# B301B.net
KiCad netlist of a schematic drawn in EAGLE
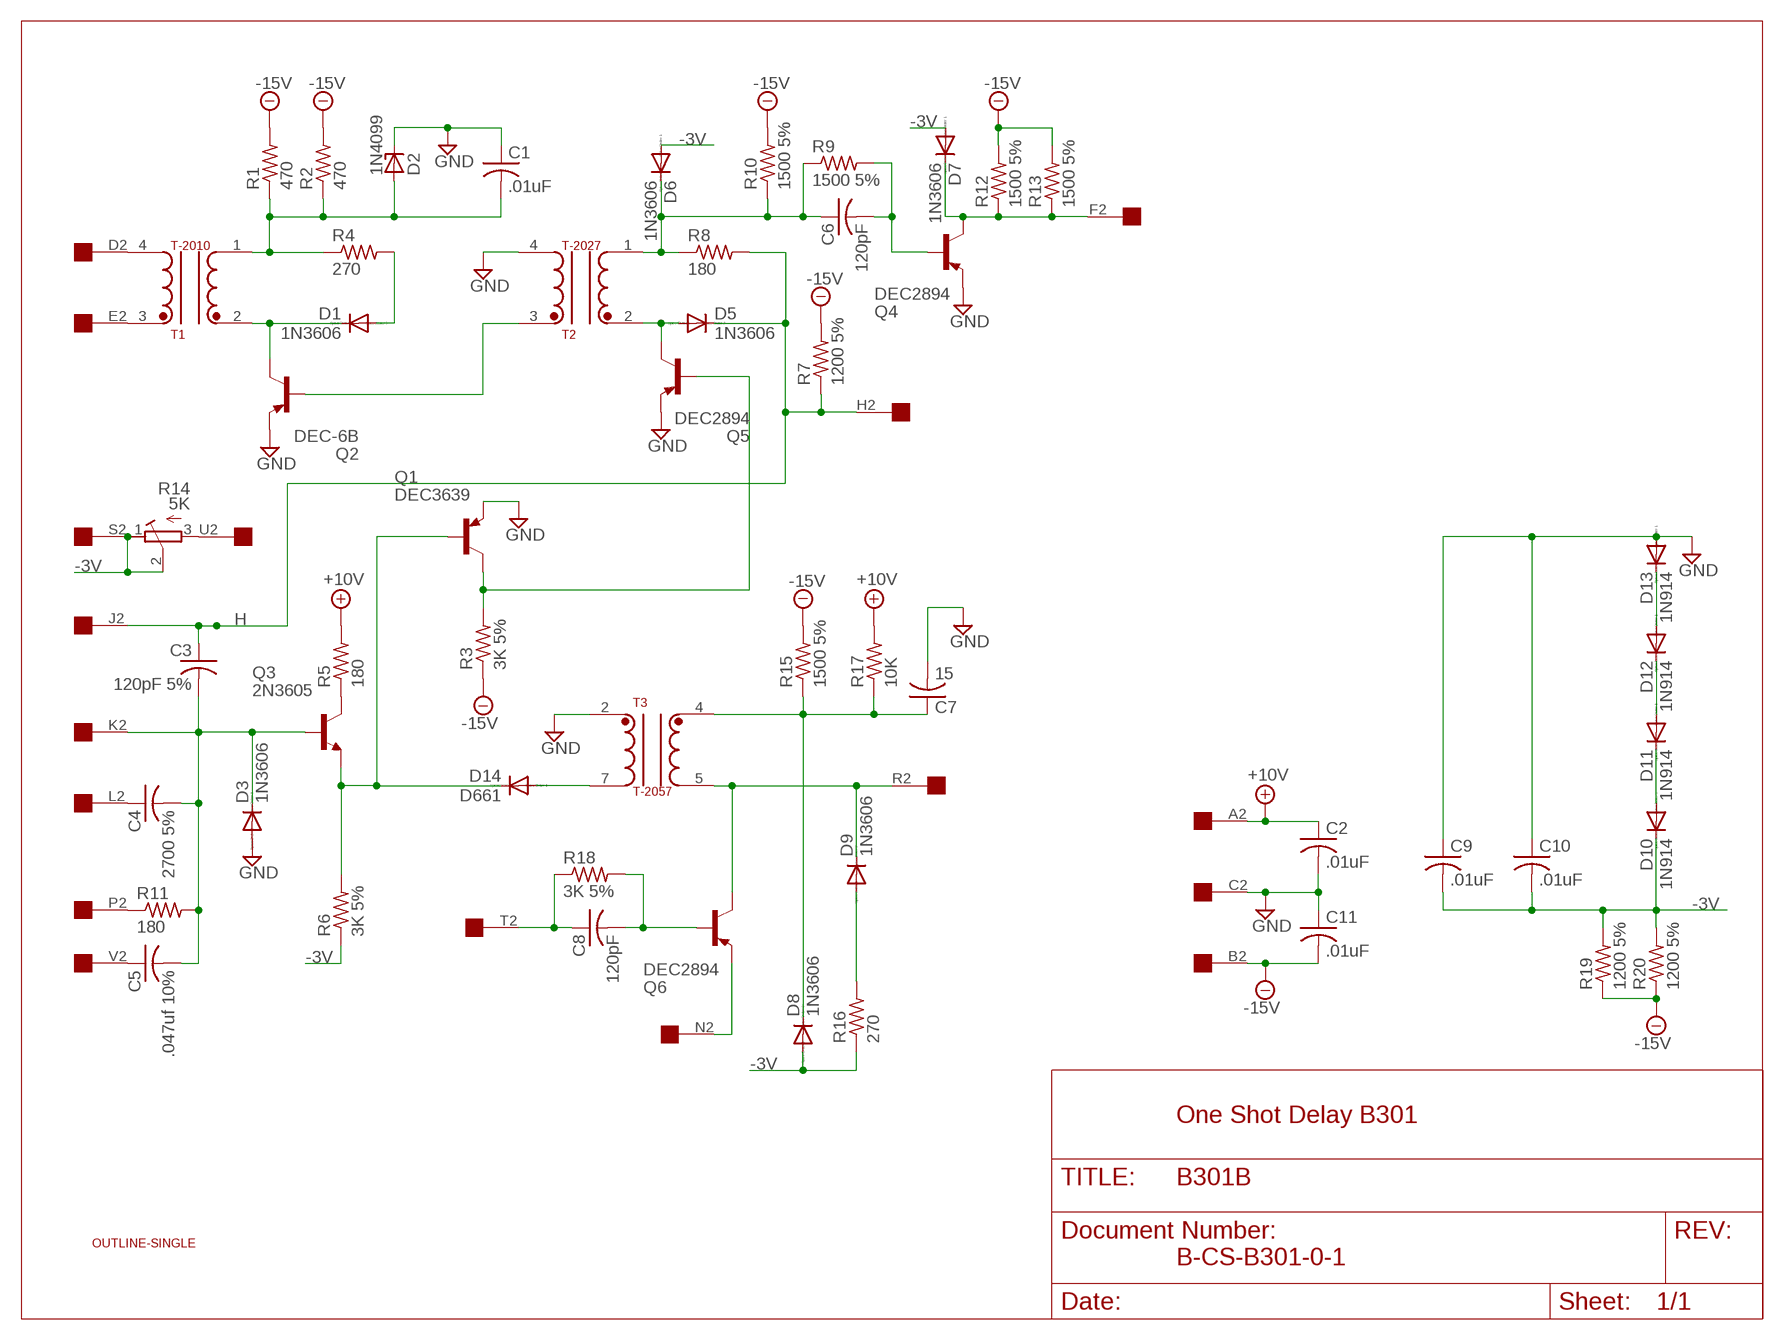
[diagram p0: schematic, sheet 1]

(export (version "E")
  (design (tool "Eeschema 10.0.6"))
  (components
    (comp (ref "C1")
      (value ".01uF")
      (footprint "eagle-import:C050-025X075")
      (libsource (lib "eagle-import") (part "C-US050-025X075"))
    )
    (comp (ref "C2")
      (value ".01uF")
      (footprint "eagle-import:C050-025X075")
      (libsource (lib "eagle-import") (part "C-US050-025X075"))
    )
    (comp (ref "C3")
      (value "120pF 5%")
      (footprint "eagle-import:C050-025X075")
      (libsource (lib "eagle-import") (part "C-US050-025X075"))
    )
    (comp (ref "C4")
      (value "2700 5%")
      (footprint "eagle-import:C102-043X133")
      (libsource (lib "eagle-import") (part "C-US102-043X133"))
    )
    (comp (ref "C5")
      (value ".047uf 10%")
      (footprint "eagle-import:C225-062X268")
      (libsource (lib "eagle-import") (part "C-US225-062X268"))
    )
    (comp (ref "C6")
      (value "120pF")
      (footprint "eagle-import:C050-025X075")
      (libsource (lib "eagle-import") (part "C-US050-025X075"))
    )
    (comp (ref "C7")
      (value "15")
      (footprint "eagle-import:C050-025X075")
      (libsource (lib "eagle-import") (part "C-US050-025X075"))
    )
    (comp (ref "C8")
      (value "120pF")
      (footprint "eagle-import:C050-025X075")
      (libsource (lib "eagle-import") (part "C-US050-025X075"))
    )
    (comp (ref "C9")
      (value ".01uF")
      (footprint "eagle-import:C050-025X075")
      (libsource (lib "eagle-import") (part "C-US050-025X075"))
    )
    (comp (ref "C10")
      (value ".01uF")
      (footprint "eagle-import:C050-025X075")
      (libsource (lib "eagle-import") (part "C-US050-025X075"))
    )
    (comp (ref "C11")
      (value ".01uF")
      (footprint "eagle-import:C050-025X075")
      (libsource (lib "eagle-import") (part "C-US050-025X075"))
    )
    (comp (ref "D1")
      (value "1N3606")
      (footprint "eagle-import:DO35-10")
      (libsource (lib "eagle-import") (part "1N4148DO35-10"))
    )
    (comp (ref "D2")
      (value "1N4099")
      (footprint "eagle-import:DO35Z10")
      (libsource (lib "eagle-import") (part "ZENER-DIODEDO35Z10"))
    )
    (comp (ref "D3")
      (value "1N3606")
      (footprint "eagle-import:DO35-10")
      (libsource (lib "eagle-import") (part "1N4148DO35-10"))
    )
    (comp (ref "D5")
      (value "1N3606")
      (footprint "eagle-import:DO35-10")
      (libsource (lib "eagle-import") (part "1N4148DO35-10"))
    )
    (comp (ref "D6")
      (value "1N3606")
      (footprint "eagle-import:DO35-10")
      (libsource (lib "eagle-import") (part "1N4148DO35-10"))
    )
    (comp (ref "D7")
      (value "1N3606")
      (footprint "eagle-import:DO35-10")
      (libsource (lib "eagle-import") (part "1N4148DO35-10"))
    )
    (comp (ref "D8")
      (value "1N3606")
      (footprint "eagle-import:DO35-10")
      (libsource (lib "eagle-import") (part "1N4148DO35-10"))
    )
    (comp (ref "D9")
      (value "1N3606")
      (footprint "eagle-import:DO35-10")
      (libsource (lib "eagle-import") (part "1N4148DO35-10"))
    )
    (comp (ref "D10")
      (value "1N914")
      (footprint "eagle-import:DO35-10")
      (libsource (lib "eagle-import") (part "1N4148DO35-10"))
    )
    (comp (ref "D11")
      (value "1N914")
      (footprint "eagle-import:DO35-10")
      (libsource (lib "eagle-import") (part "1N4148DO35-10"))
    )
    (comp (ref "D12")
      (value "1N914")
      (footprint "eagle-import:DO35-10")
      (libsource (lib "eagle-import") (part "1N4148DO35-10"))
    )
    (comp (ref "D13")
      (value "1N914")
      (footprint "eagle-import:DO35-10")
      (libsource (lib "eagle-import") (part "1N4148DO35-10"))
    )
    (comp (ref "D14")
      (value "D661")
      (footprint "eagle-import:DO35-10")
      (libsource (lib "eagle-import") (part "1N4148DO35-10"))
    )
    (comp (ref "Q1")
      (value "DEC3639")
      (footprint "eagle-import:TO39")
      (libsource (lib "eagle-import") (part "2N2904"))
    )
    (comp (ref "Q2")
      (value "DEC-6B")
      (footprint "eagle-import:TO39")
      (libsource (lib "eagle-import") (part "2N2904"))
    )
    (comp (ref "Q3")
      (value "2N3605")
      (footprint "eagle-import:TO39")
      (libsource (lib "eagle-import") (part "-NPN-TO39-EBC2N2102"))
    )
    (comp (ref "Q4")
      (value "DEC2894")
      (footprint "eagle-import:TO39")
      (libsource (lib "eagle-import") (part "2N2904"))
    )
    (comp (ref "Q5")
      (value "DEC2894")
      (footprint "eagle-import:TO39")
      (libsource (lib "eagle-import") (part "2N2904"))
    )
    (comp (ref "Q6")
      (value "DEC2894")
      (footprint "eagle-import:TO39")
      (libsource (lib "eagle-import") (part "2N2904"))
    )
    (comp (ref "R1")
      (value "470")
      (footprint "eagle-import:0207_10")
      (libsource (lib "eagle-import") (part "R-US_0207/10"))
    )
    (comp (ref "R2")
      (value "470")
      (footprint "eagle-import:0207_10")
      (libsource (lib "eagle-import") (part "R-US_0207/10"))
    )
    (comp (ref "R3")
      (value "3K 5%")
      (footprint "eagle-import:0207_10")
      (libsource (lib "eagle-import") (part "R-US_0207/10"))
    )
    (comp (ref "R4")
      (value "270")
      (footprint "eagle-import:0207_10")
      (libsource (lib "eagle-import") (part "R-US_0207/10"))
    )
    (comp (ref "R5")
      (value "180")
      (footprint "eagle-import:0207_10")
      (libsource (lib "eagle-import") (part "R-US_0207/10"))
    )
    (comp (ref "R6")
      (value "3K 5%")
      (footprint "eagle-import:0207_10")
      (libsource (lib "eagle-import") (part "R-US_0207/10"))
    )
    (comp (ref "R7")
      (value "1200 5%")
      (footprint "eagle-import:0207_10")
      (libsource (lib "eagle-import") (part "R-US_0207/10"))
    )
    (comp (ref "R8")
      (value "180")
      (footprint "eagle-import:0207_10")
      (libsource (lib "eagle-import") (part "R-US_0207/10"))
    )
    (comp (ref "R9")
      (value "1500 5%")
      (footprint "eagle-import:0207_10")
      (libsource (lib "eagle-import") (part "R-US_0207/10"))
    )
    (comp (ref "R10")
      (value "1500 5%")
      (footprint "eagle-import:0207_10")
      (libsource (lib "eagle-import") (part "R-US_0207/10"))
    )
    (comp (ref "R11")
      (value "180")
      (footprint "eagle-import:0207_10")
      (libsource (lib "eagle-import") (part "R-US_0207/10"))
    )
    (comp (ref "R12")
      (value "1500 5%")
      (footprint "eagle-import:0207_10")
      (libsource (lib "eagle-import") (part "R-US_0207/10"))
    )
    (comp (ref "R13")
      (value "1500 5%")
      (footprint "eagle-import:0207_10")
      (libsource (lib "eagle-import") (part "R-US_0207/10"))
    )
    (comp (ref "R14")
      (value "5K")
      (footprint "eagle-import:3006Y")
      (libsource (lib "eagle-import") (part "275P"))
    )
    (comp (ref "R15")
      (value "1500 5%")
      (footprint "eagle-import:0207_10")
      (libsource (lib "eagle-import") (part "R-US_0207/10"))
    )
    (comp (ref "R16")
      (value "270")
      (footprint "eagle-import:0207_10")
      (libsource (lib "eagle-import") (part "R-US_0207/10"))
    )
    (comp (ref "R17")
      (value "10K")
      (footprint "eagle-import:0207_10")
      (libsource (lib "eagle-import") (part "R-US_0207/10"))
    )
    (comp (ref "R18")
      (value "3K 5%")
      (footprint "eagle-import:0207_10")
      (libsource (lib "eagle-import") (part "R-US_0207/10"))
    )
    (comp (ref "R19")
      (value "1200 5%")
      (footprint "eagle-import:0207_10")
      (libsource (lib "eagle-import") (part "R-US_0207/10"))
    )
    (comp (ref "R20")
      (value "1200 5%")
      (footprint "eagle-import:0207_10")
      (libsource (lib "eagle-import") (part "R-US_0207/10"))
    )
    (comp (ref "T1")
      (value "T-2010")
      (footprint "eagle-import:TRANSFORMER2")
      (libsource (lib "eagle-import") (part "T-2010"))
    )
    (comp (ref "T2")
      (value "T-2027")
      (footprint "eagle-import:TRANSFORMER2")
      (libsource (lib "eagle-import") (part "T-2010"))
    )
    (comp (ref "T3")
      (value "T-2057")
      (footprint "eagle-import:TRANSFORMER")
      (libsource (lib "eagle-import") (part "T-2037"))
    )
    (comp (ref "U$1")
      (value "OUTLINE-SINGLE")
      (footprint "eagle-import:SINGLE")
      (libsource (lib "eagle-import") (part "OUTLINE-SINGLE"))
    )
    (comp (ref "U$2")
      (value "EDGE-1")
      (footprint "eagle-import:EDGE-CON1")
      (libsource (lib "eagle-import") (part "EDGE-1"))
    )
  )
  (nets
    (net (code "1") (name "+10V") (class "Default")
      (node (ref "C2") (pin "1") (pinfunction "1_1") (pintype "passive"))
      (node (ref "R17") (pin "2") (pinfunction "2_2") (pintype "passive"))
      (node (ref "R5") (pin "2") (pinfunction "2_2") (pintype "passive"))
      (node (ref "U$2") (pin "A2") (pinfunction "1_A2") (pintype "bidirectional"))
    )
    (net (code "2") (name "-15V") (class "Default")
      (node (ref "C11") (pin "2") (pinfunction "2_2") (pintype "passive"))
      (node (ref "R1") (pin "2") (pinfunction "2_2") (pintype "passive"))
      (node (ref "R10") (pin "2") (pinfunction "2_2") (pintype "passive"))
      (node (ref "R12") (pin "2") (pinfunction "2_2") (pintype "passive"))
      (node (ref "R13") (pin "2") (pinfunction "2_2") (pintype "passive"))
      (node (ref "R15") (pin "2") (pinfunction "2_2") (pintype "passive"))
      (node (ref "R19") (pin "1") (pinfunction "1_1") (pintype "passive"))
      (node (ref "R2") (pin "2") (pinfunction "2_2") (pintype "passive"))
      (node (ref "R20") (pin "1") (pinfunction "1_1") (pintype "passive"))
      (node (ref "R3") (pin "1") (pinfunction "1_1") (pintype "passive"))
      (node (ref "R7") (pin "2") (pinfunction "2_2") (pintype "passive"))
      (node (ref "U$2") (pin "B2") (pinfunction "1_B2") (pintype "bidirectional"))
    )
    (net (code "3") (name "/-3V") (class "Default")
      (node (ref "C10") (pin "2") (pinfunction "2_2") (pintype "passive"))
      (node (ref "C9") (pin "2") (pinfunction "2_2") (pintype "passive"))
      (node (ref "D10") (pin "C") (pinfunction "C_C") (pintype "passive"))
      (node (ref "D6") (pin "A") (pinfunction "A_A") (pintype "passive"))
      (node (ref "D7") (pin "A") (pinfunction "A_A") (pintype "passive"))
      (node (ref "D8") (pin "A") (pinfunction "A_A") (pintype "passive"))
      (node (ref "R14") (pin "1") (pinfunction "A_1") (pintype "passive"))
      (node (ref "R14") (pin "2") (pinfunction "S_2") (pintype "passive"))
      (node (ref "R16") (pin "1") (pinfunction "1_1") (pintype "passive"))
      (node (ref "R19") (pin "2") (pinfunction "2_2") (pintype "passive"))
      (node (ref "R20") (pin "2") (pinfunction "2_2") (pintype "passive"))
      (node (ref "R6") (pin "1") (pinfunction "1_1") (pintype "passive"))
      (node (ref "U$2") (pin "S2") (pinfunction "1_S2") (pintype "bidirectional"))
    )
    (net (code "4") (name "/H") (class "Default")
      (node (ref "C3") (pin "1") (pinfunction "1_1") (pintype "passive"))
      (node (ref "D5") (pin "C") (pinfunction "C_C") (pintype "passive"))
      (node (ref "R7") (pin "1") (pinfunction "1_1") (pintype "passive"))
      (node (ref "R8") (pin "2") (pinfunction "2_2") (pintype "passive"))
      (node (ref "U$2") (pin "H2") (pinfunction "1_H2") (pintype "bidirectional"))
      (node (ref "U$2") (pin "J2") (pinfunction "1_J2") (pintype "bidirectional"))
    )
    (net (code "5") (name "GND") (class "Default")
      (node (ref "C1") (pin "1") (pinfunction "1_1") (pintype "passive"))
      (node (ref "C10") (pin "1") (pinfunction "1_1") (pintype "passive"))
      (node (ref "C11") (pin "1") (pinfunction "1_1") (pintype "passive"))
      (node (ref "C2") (pin "2") (pinfunction "2_2") (pintype "passive"))
      (node (ref "C7") (pin "2") (pinfunction "2_2") (pintype "passive"))
      (node (ref "C9") (pin "1") (pinfunction "1_1") (pintype "passive"))
      (node (ref "D13") (pin "A") (pinfunction "A_A") (pintype "passive"))
      (node (ref "D2") (pin "C") (pinfunction "C_C") (pintype "passive"))
      (node (ref "D3") (pin "A") (pinfunction "A_A") (pintype "passive"))
      (node (ref "Q1") (pin "1") (pinfunction "E_1") (pintype "passive"))
      (node (ref "Q2") (pin "1") (pinfunction "E_1") (pintype "passive"))
      (node (ref "Q4") (pin "1") (pinfunction "E_1") (pintype "passive"))
      (node (ref "Q5") (pin "1") (pinfunction "E_1") (pintype "passive"))
      (node (ref "T2") (pin "4") (pinfunction "P$7_4") (pintype "passive"))
      (node (ref "T3") (pin "2") (pinfunction "P$2_2") (pintype "passive"))
      (node (ref "U$2") (pin "C2") (pinfunction "1_C2") (pintype "bidirectional"))
    )
    (net (code "6") (name "Net-(D1-PadA)") (class "Default")
      (node (ref "D1") (pin "A") (pinfunction "A_A") (pintype "passive"))
      (node (ref "R4") (pin "2") (pinfunction "2_2") (pintype "passive"))
    )
    (net (code "7") (name "Net-(D9-PadA)") (class "Default")
      (node (ref "D9") (pin "A") (pinfunction "A_A") (pintype "passive"))
      (node (ref "R16") (pin "2") (pinfunction "2_2") (pintype "passive"))
    )
    (net (code "8") (name "Net-(D10-PadA)") (class "Default")
      (node (ref "D10") (pin "A") (pinfunction "A_A") (pintype "passive"))
      (node (ref "D11") (pin "C") (pinfunction "C_C") (pintype "passive"))
    )
    (net (code "9") (name "Net-(D11-PadA)") (class "Default")
      (node (ref "D11") (pin "A") (pinfunction "A_A") (pintype "passive"))
      (node (ref "D12") (pin "C") (pinfunction "C_C") (pintype "passive"))
    )
    (net (code "10") (name "Net-(D12-PadA)") (class "Default")
      (node (ref "D12") (pin "A") (pinfunction "A_A") (pintype "passive"))
      (node (ref "D13") (pin "C") (pinfunction "C_C") (pintype "passive"))
    )
    (net (code "11") (name "Net-(Q1-B)") (class "Default")
      (node (ref "D14") (pin "C") (pinfunction "C_C") (pintype "passive"))
      (node (ref "Q1") (pin "2") (pinfunction "B_2") (pintype "passive"))
      (node (ref "Q3") (pin "1") (pinfunction "E_1") (pintype "passive"))
      (node (ref "R6") (pin "2") (pinfunction "2_2") (pintype "passive"))
    )
    (net (code "12") (name "Net-(Q1-C)") (class "Default")
      (node (ref "Q1") (pin "3") (pinfunction "C_3") (pintype "passive"))
      (node (ref "Q5") (pin "2") (pinfunction "B_2") (pintype "passive"))
      (node (ref "R3") (pin "2") (pinfunction "2_2") (pintype "passive"))
    )
    (net (code "13") (name "Net-(Q2-B)") (class "Default")
      (node (ref "Q2") (pin "2") (pinfunction "B_2") (pintype "passive"))
      (node (ref "T2") (pin "3") (pinfunction "P$2_3") (pintype "passive"))
    )
    (net (code "14") (name "Net-(Q2-C)") (class "Default")
      (node (ref "D1") (pin "C") (pinfunction "C_C") (pintype "passive"))
      (node (ref "Q2") (pin "3") (pinfunction "C_3") (pintype "passive"))
      (node (ref "T1") (pin "2") (pinfunction "P$4_2") (pintype "passive"))
    )
    (net (code "15") (name "Net-(Q3-B)") (class "Default")
      (node (ref "C3") (pin "2") (pinfunction "2_2") (pintype "passive"))
      (node (ref "C4") (pin "2") (pinfunction "2_2") (pintype "passive"))
      (node (ref "C5") (pin "2") (pinfunction "2_2") (pintype "passive"))
      (node (ref "D3") (pin "C") (pinfunction "C_C") (pintype "passive"))
      (node (ref "Q3") (pin "2") (pinfunction "B_2") (pintype "passive"))
      (node (ref "R11") (pin "2") (pinfunction "2_2") (pintype "passive"))
      (node (ref "U$2") (pin "K2") (pinfunction "1_K2") (pintype "bidirectional"))
    )
    (net (code "16") (name "Net-(Q3-C)") (class "Default")
      (node (ref "Q3") (pin "3") (pinfunction "C_3") (pintype "passive"))
      (node (ref "R5") (pin "1") (pinfunction "1_1") (pintype "passive"))
    )
    (net (code "17") (name "Net-(Q4-B)") (class "Default")
      (node (ref "C6") (pin "2") (pinfunction "2_2") (pintype "passive"))
      (node (ref "Q4") (pin "2") (pinfunction "B_2") (pintype "passive"))
      (node (ref "R9") (pin "2") (pinfunction "2_2") (pintype "passive"))
    )
    (net (code "18") (name "Net-(Q4-C)") (class "Default")
      (node (ref "D7") (pin "C") (pinfunction "C_C") (pintype "passive"))
      (node (ref "Q4") (pin "3") (pinfunction "C_3") (pintype "passive"))
      (node (ref "R12") (pin "1") (pinfunction "1_1") (pintype "passive"))
      (node (ref "R13") (pin "1") (pinfunction "1_1") (pintype "passive"))
      (node (ref "U$2") (pin "F2") (pinfunction "1_F2") (pintype "bidirectional"))
    )
    (net (code "19") (name "Net-(Q5-C)") (class "Default")
      (node (ref "D5") (pin "A") (pinfunction "A_A") (pintype "passive"))
      (node (ref "Q5") (pin "3") (pinfunction "C_3") (pintype "passive"))
      (node (ref "T2") (pin "2") (pinfunction "P$4_2") (pintype "passive"))
    )
    (net (code "20") (name "Net-(Q6-B)") (class "Default")
      (node (ref "C8") (pin "2") (pinfunction "2_2") (pintype "passive"))
      (node (ref "Q6") (pin "2") (pinfunction "B_2") (pintype "passive"))
      (node (ref "R18") (pin "2") (pinfunction "2_2") (pintype "passive"))
    )
    (net (code "21") (name "Net-(Q6-C)") (class "Default")
      (node (ref "D9") (pin "C") (pinfunction "C_C") (pintype "passive"))
      (node (ref "Q6") (pin "3") (pinfunction "C_3") (pintype "passive"))
      (node (ref "T3") (pin "5") (pinfunction "P$5_5") (pintype "passive"))
      (node (ref "U$2") (pin "R2") (pinfunction "1_R2") (pintype "bidirectional"))
    )
    (net (code "22") (name "Net-(Q6-E)") (class "Default")
      (node (ref "Q6") (pin "1") (pinfunction "E_1") (pintype "passive"))
      (node (ref "U$2") (pin "N2") (pinfunction "1_N2") (pintype "bidirectional"))
    )
    (net (code "23") (name "Net-(R14-E)") (class "Default")
      (node (ref "R14") (pin "3") (pinfunction "E_3") (pintype "passive"))
      (node (ref "U$2") (pin "U2") (pinfunction "1_U2") (pintype "bidirectional"))
    )
    (net (code "24") (name "Net-(T1-P$2)") (class "Default")
      (node (ref "T1") (pin "3") (pinfunction "P$2_3") (pintype "passive"))
      (node (ref "U$2") (pin "E2") (pinfunction "1_E2") (pintype "bidirectional"))
    )
    (net (code "25") (name "Net-(T1-P$5)") (class "Default")
      (node (ref "C1") (pin "2") (pinfunction "2_2") (pintype "passive"))
      (node (ref "D2") (pin "A") (pinfunction "A_A") (pintype "passive"))
      (node (ref "R1") (pin "1") (pinfunction "1_1") (pintype "passive"))
      (node (ref "R2") (pin "1") (pinfunction "1_1") (pintype "passive"))
      (node (ref "R4") (pin "1") (pinfunction "1_1") (pintype "passive"))
      (node (ref "T1") (pin "1") (pinfunction "P$5_1") (pintype "passive"))
    )
    (net (code "26") (name "Net-(T1-P$7)") (class "Default")
      (node (ref "T1") (pin "4") (pinfunction "P$7_4") (pintype "passive"))
      (node (ref "U$2") (pin "D2") (pinfunction "1_D2") (pintype "bidirectional"))
    )
    (net (code "27") (name "Net-(T2-P$5)") (class "Default")
      (node (ref "C6") (pin "1") (pinfunction "1_1") (pintype "passive"))
      (node (ref "D6") (pin "C") (pinfunction "C_C") (pintype "passive"))
      (node (ref "R10") (pin "1") (pinfunction "1_1") (pintype "passive"))
      (node (ref "R8") (pin "1") (pinfunction "1_1") (pintype "passive"))
      (node (ref "R9") (pin "1") (pinfunction "1_1") (pintype "passive"))
      (node (ref "T2") (pin "1") (pinfunction "P$5_1") (pintype "passive"))
    )
    (net (code "28") (name "Net-(T3-P$4)") (class "Default")
      (node (ref "C7") (pin "1") (pinfunction "1_1") (pintype "passive"))
      (node (ref "D8") (pin "C") (pinfunction "C_C") (pintype "passive"))
      (node (ref "R15") (pin "1") (pinfunction "1_1") (pintype "passive"))
      (node (ref "R17") (pin "1") (pinfunction "1_1") (pintype "passive"))
      (node (ref "T3") (pin "4") (pinfunction "P$4_4") (pintype "passive"))
    )
    (net (code "29") (name "Net-(T3-P$7)") (class "Default")
      (node (ref "D14") (pin "A") (pinfunction "A_A") (pintype "passive"))
      (node (ref "T3") (pin "7") (pinfunction "P$7_7") (pintype "passive"))
    )
    (net (code "30") (name "Net-(U$2J-1)") (class "Default")
      (node (ref "C4") (pin "1") (pinfunction "1_1") (pintype "passive"))
      (node (ref "U$2") (pin "L2") (pinfunction "1_L2") (pintype "bidirectional"))
    )
    (net (code "31") (name "Net-(U$2M-1)") (class "Default")
      (node (ref "R11") (pin "1") (pinfunction "1_1") (pintype "passive"))
      (node (ref "U$2") (pin "P2") (pinfunction "1_P2") (pintype "bidirectional"))
    )
    (net (code "32") (name "Net-(U$2P-1)") (class "Default")
      (node (ref "C8") (pin "1") (pinfunction "1_1") (pintype "passive"))
      (node (ref "R18") (pin "1") (pinfunction "1_1") (pintype "passive"))
      (node (ref "U$2") (pin "T2") (pinfunction "1_T2") (pintype "bidirectional"))
    )
    (net (code "33") (name "Net-(U$2R-1)") (class "Default")
      (node (ref "C5") (pin "1") (pinfunction "1_1") (pintype "passive"))
      (node (ref "U$2") (pin "V2") (pinfunction "1_V2") (pintype "bidirectional"))
    )
  )
)
